# uv-exposure-box-main-v2.net
KiCad netlist of a schematic drawn in EAGLE
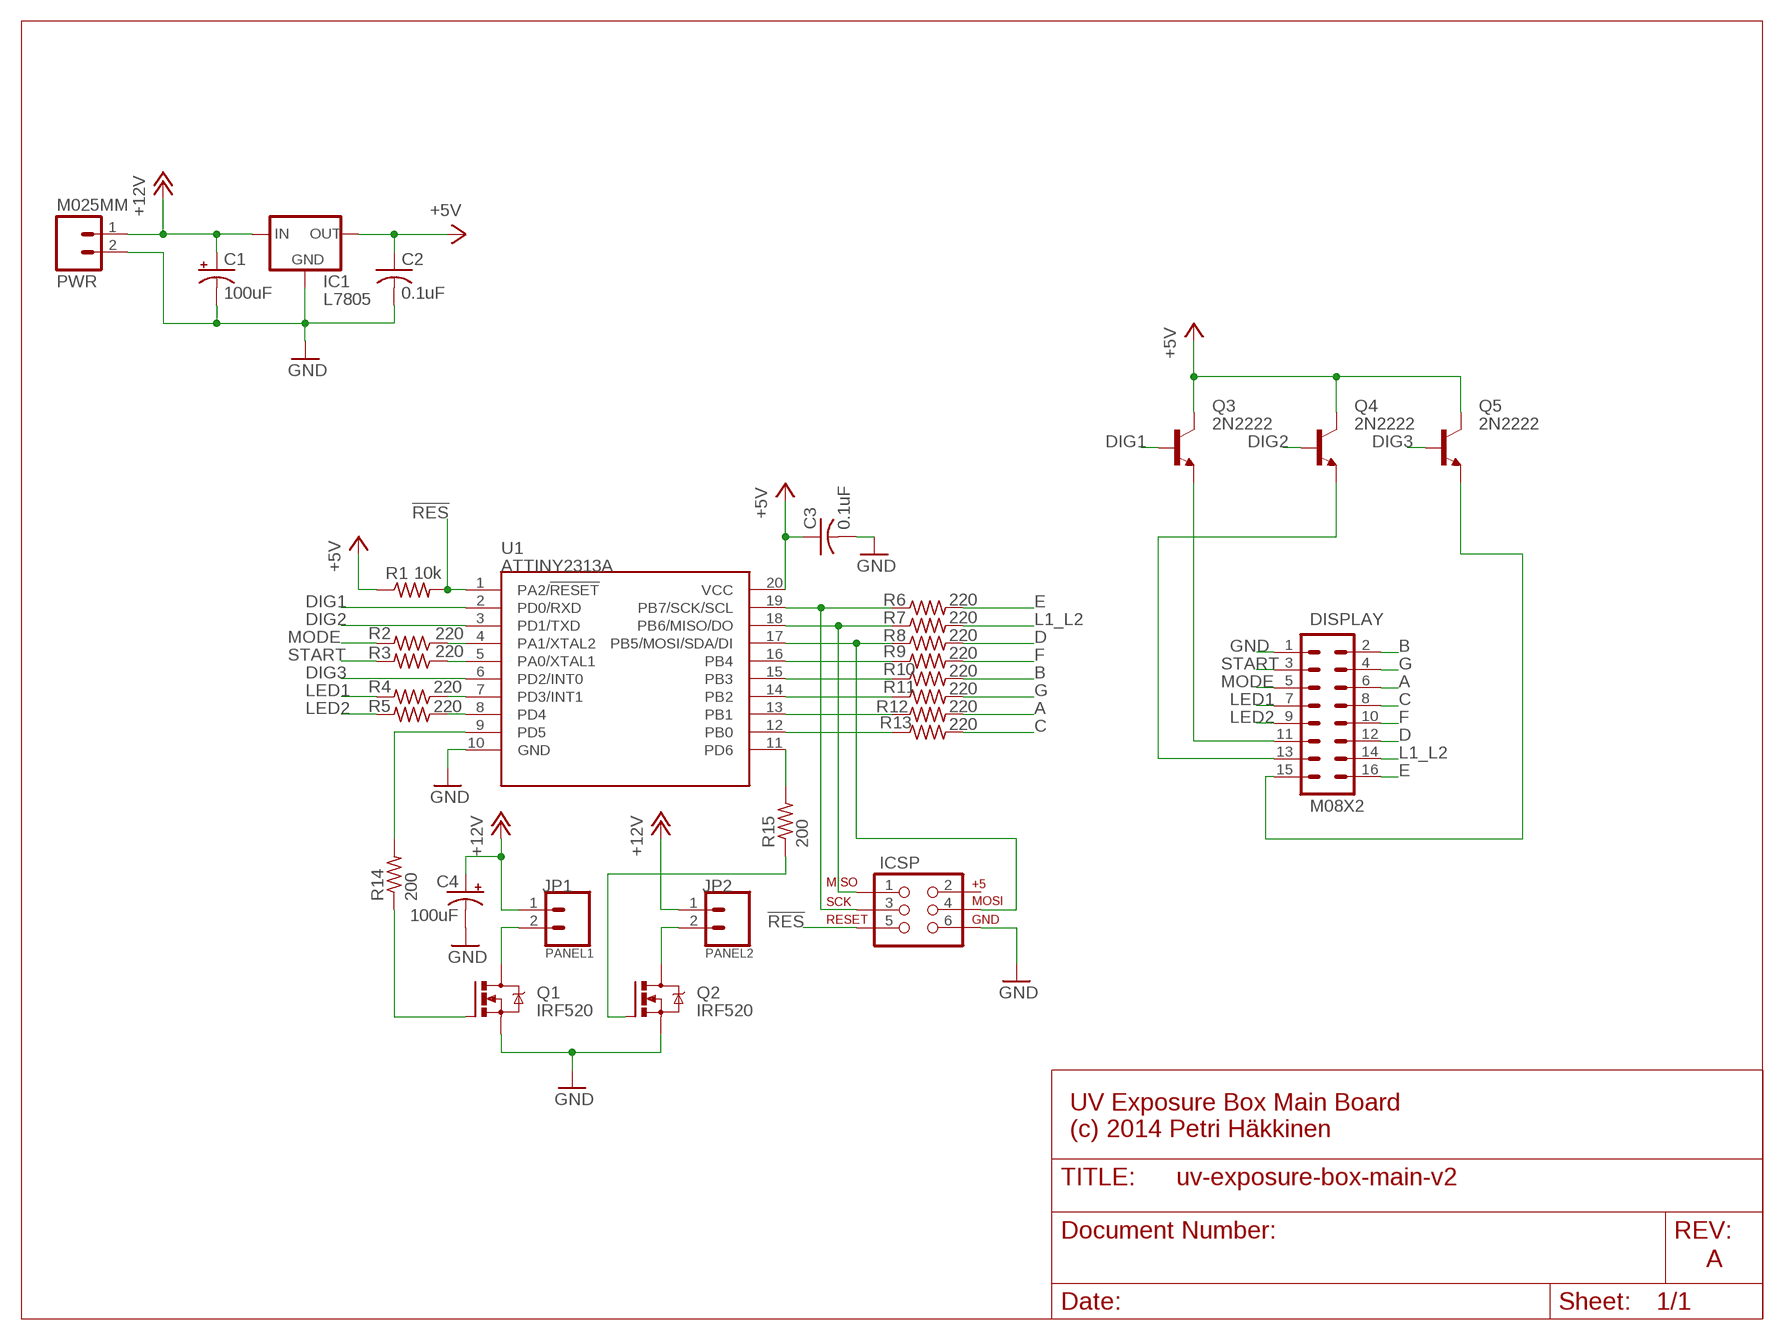
[diagram p0: schematic, sheet 1]

(export (version "E")
  (design (tool "Eeschema 10.0.6"))
  (components
    (comp (ref "C1")
      (value "100uF")
      (footprint "eagle-import:E2,5-5")
      (libsource (lib "eagle-import") (part "CPOL-USE2.5-5"))
    )
    (comp (ref "C2")
      (value "0.1uF")
      (footprint "eagle-import:C025-024X044")
      (libsource (lib "eagle-import") (part "C-US025-024X044"))
    )
    (comp (ref "C3")
      (value "0.1uF")
      (footprint "eagle-import:C025-024X044")
      (libsource (lib "eagle-import") (part "C-US025-024X044"))
    )
    (comp (ref "C4")
      (value "100uF")
      (footprint "eagle-import:E2,5-5")
      (libsource (lib "eagle-import") (part "CPOL-USE2.5-5"))
    )
    (comp (ref "DISPLAY")
      (value "M08X2")
      (footprint "eagle-import:2X8")
      (libsource (lib "eagle-import") (part "M08X2"))
    )
    (comp (ref "IC1")
      (value "L7805")
      (footprint "eagle-import:TO220-IGO")
      (libsource (lib "eagle-import") (part "V_REG_78XXV"))
    )
    (comp (ref "ICSP")
      (value "AVR_SPI_PRG_6PTH")
      (footprint "eagle-import:2X3")
      (libsource (lib "eagle-import") (part "AVR_SPI_PRG_6PTH"))
    )
    (comp (ref "JP1")
      (value "M025MM")
      (footprint "eagle-import:SCREWTERMINAL-5MM-2")
      (libsource (lib "eagle-import") (part "M025MM"))
    )
    (comp (ref "JP2")
      (value "M025MM")
      (footprint "eagle-import:SCREWTERMINAL-5MM-2")
      (libsource (lib "eagle-import") (part "M025MM"))
    )
    (comp (ref "PWR")
      (value "M025MM")
      (footprint "eagle-import:SCREWTERMINAL-5MM-2")
      (libsource (lib "eagle-import") (part "M025MM"))
    )
    (comp (ref "Q1")
      (value "IRF520")
      (footprint "eagle-import:TO220BV")
      (libsource (lib "eagle-import") (part "IRF520"))
    )
    (comp (ref "Q2")
      (value "IRF520")
      (footprint "eagle-import:TO220BV")
      (libsource (lib "eagle-import") (part "IRF520"))
    )
    (comp (ref "Q3")
      (value "2N2222")
      (footprint "eagle-import:TO92-EBC")
      (libsource (lib "eagle-import") (part "-NPN-TO92-EBC2N2222"))
    )
    (comp (ref "Q4")
      (value "2N2222")
      (footprint "eagle-import:TO92-EBC")
      (libsource (lib "eagle-import") (part "-NPN-TO92-EBC2N2222"))
    )
    (comp (ref "Q5")
      (value "2N2222")
      (footprint "eagle-import:TO92-EBC")
      (libsource (lib "eagle-import") (part "-NPN-TO92-EBC2N2222"))
    )
    (comp (ref "R1")
      (value "10k")
      (footprint "eagle-import:0207_10")
      (libsource (lib "eagle-import") (part "R-US_0207/10"))
    )
    (comp (ref "R2")
      (value "220")
      (footprint "eagle-import:0207_10")
      (libsource (lib "eagle-import") (part "R-US_0207/10"))
    )
    (comp (ref "R3")
      (value "220")
      (footprint "eagle-import:0207_10")
      (libsource (lib "eagle-import") (part "R-US_0207/10"))
    )
    (comp (ref "R4")
      (value "220")
      (footprint "eagle-import:0207_10")
      (libsource (lib "eagle-import") (part "R-US_0207/10"))
    )
    (comp (ref "R5")
      (value "220")
      (footprint "eagle-import:0207_10")
      (libsource (lib "eagle-import") (part "R-US_0207/10"))
    )
    (comp (ref "R6")
      (value "220")
      (footprint "eagle-import:0207_10")
      (libsource (lib "eagle-import") (part "R-US_0207/10"))
    )
    (comp (ref "R7")
      (value "220")
      (footprint "eagle-import:0207_10")
      (libsource (lib "eagle-import") (part "R-US_0207/10"))
    )
    (comp (ref "R8")
      (value "220")
      (footprint "eagle-import:0207_10")
      (libsource (lib "eagle-import") (part "R-US_0207/10"))
    )
    (comp (ref "R9")
      (value "220")
      (footprint "eagle-import:0207_10")
      (libsource (lib "eagle-import") (part "R-US_0207/10"))
    )
    (comp (ref "R10")
      (value "220")
      (footprint "eagle-import:0207_10")
      (libsource (lib "eagle-import") (part "R-US_0207/10"))
    )
    (comp (ref "R11")
      (value "220")
      (footprint "eagle-import:0207_10")
      (libsource (lib "eagle-import") (part "R-US_0207/10"))
    )
    (comp (ref "R12")
      (value "220")
      (footprint "eagle-import:0207_10")
      (libsource (lib "eagle-import") (part "R-US_0207/10"))
    )
    (comp (ref "R13")
      (value "220")
      (footprint "eagle-import:0207_10")
      (libsource (lib "eagle-import") (part "R-US_0207/10"))
    )
    (comp (ref "R14")
      (value "200")
      (footprint "eagle-import:0207_10")
      (libsource (lib "eagle-import") (part "R-US_0207/10"))
    )
    (comp (ref "R15")
      (value "200")
      (footprint "eagle-import:0207_10")
      (libsource (lib "eagle-import") (part "R-US_0207/10"))
    )
    (comp (ref "U1")
      (value "ATTINY2313A")
      (footprint "eagle-import:DIL20")
      (libsource (lib "eagle-import") (part "ATTINY2313ADIL20"))
    )
  )
  (nets
    (net (code "1") (name "+5V") (class "Default")
      (node (ref "C2") (pin "1") (pinfunction "1_1") (pintype "passive"))
      (node (ref "C3") (pin "1") (pinfunction "1_1") (pintype "passive"))
      (node (ref "IC1") (pin "OUT") (pinfunction "OUT_OUT") (pintype "output"))
      (node (ref "Q3") (pin "C") (pinfunction "C_C") (pintype "passive"))
      (node (ref "Q4") (pin "C") (pinfunction "C_C") (pintype "passive"))
      (node (ref "Q5") (pin "C") (pinfunction "C_C") (pintype "passive"))
      (node (ref "R1") (pin "1") (pinfunction "1_1") (pintype "passive"))
      (node (ref "U1") (pin "20") (pinfunction "VCC_20") (pintype "bidirectional"))
    )
    (net (code "2") (name "+12V") (class "Default")
      (node (ref "C1") (pin "+") (pinfunction "+_+") (pintype "passive"))
      (node (ref "C4") (pin "+") (pinfunction "+_+") (pintype "passive"))
      (node (ref "IC1") (pin "IN") (pinfunction "IN_IN") (pintype "input"))
      (node (ref "JP1") (pin "1") (pinfunction "1_1") (pintype "passive"))
      (node (ref "JP2") (pin "1") (pinfunction "1_1") (pintype "passive"))
      (node (ref "PWR") (pin "1") (pinfunction "1_1") (pintype "passive"))
    )
    (net (code "3") (name "/A") (class "Default")
      (node (ref "DISPLAY") (pin "6") (pinfunction "6_6") (pintype "passive"))
      (node (ref "R12") (pin "2") (pinfunction "2_2") (pintype "passive"))
    )
    (net (code "4") (name "/B") (class "Default")
      (node (ref "DISPLAY") (pin "2") (pinfunction "2_2") (pintype "passive"))
      (node (ref "R10") (pin "2") (pinfunction "2_2") (pintype "passive"))
    )
    (net (code "5") (name "/C") (class "Default")
      (node (ref "DISPLAY") (pin "8") (pinfunction "8_8") (pintype "passive"))
      (node (ref "R13") (pin "2") (pinfunction "2_2") (pintype "passive"))
    )
    (net (code "6") (name "/D") (class "Default")
      (node (ref "DISPLAY") (pin "12") (pinfunction "12_12") (pintype "passive"))
      (node (ref "R8") (pin "2") (pinfunction "2_2") (pintype "passive"))
    )
    (net (code "7") (name "/DIG1") (class "Default")
      (node (ref "DISPLAY") (pin "11") (pinfunction "11_11") (pintype "passive"))
      (node (ref "Q3") (pin "B") (pinfunction "B_B") (pintype "passive"))
      (node (ref "Q3") (pin "E") (pinfunction "E_E") (pintype "passive"))
      (node (ref "U1") (pin "2") (pinfunction "PD0/RXD_2") (pintype "bidirectional"))
    )
    (net (code "8") (name "/DIG2") (class "Default")
      (node (ref "Q4") (pin "B") (pinfunction "B_B") (pintype "passive"))
      (node (ref "U1") (pin "3") (pinfunction "PD1/TXD_3") (pintype "bidirectional"))
    )
    (net (code "9") (name "/DIG3") (class "Default")
      (node (ref "Q5") (pin "B") (pinfunction "B_B") (pintype "passive"))
      (node (ref "U1") (pin "6") (pinfunction "PD2/INT0_6") (pintype "bidirectional"))
    )
    (net (code "10") (name "/E") (class "Default")
      (node (ref "DISPLAY") (pin "16") (pinfunction "16_16") (pintype "passive"))
      (node (ref "R6") (pin "2") (pinfunction "2_2") (pintype "passive"))
    )
    (net (code "11") (name "/F") (class "Default")
      (node (ref "DISPLAY") (pin "10") (pinfunction "10_10") (pintype "passive"))
      (node (ref "R9") (pin "2") (pinfunction "2_2") (pintype "passive"))
    )
    (net (code "12") (name "/G") (class "Default")
      (node (ref "DISPLAY") (pin "4") (pinfunction "4_4") (pintype "passive"))
      (node (ref "R11") (pin "2") (pinfunction "2_2") (pintype "passive"))
    )
    (net (code "13") (name "/L1_L2") (class "Default")
      (node (ref "DISPLAY") (pin "14") (pinfunction "14_14") (pintype "passive"))
      (node (ref "R7") (pin "2") (pinfunction "2_2") (pintype "passive"))
    )
    (net (code "14") (name "/LED1") (class "Default")
      (node (ref "DISPLAY") (pin "7") (pinfunction "7_7") (pintype "passive"))
      (node (ref "R4") (pin "2") (pinfunction "2_2") (pintype "passive"))
    )
    (net (code "15") (name "/LED2") (class "Default")
      (node (ref "DISPLAY") (pin "9") (pinfunction "9_9") (pintype "passive"))
      (node (ref "R5") (pin "2") (pinfunction "2_2") (pintype "passive"))
    )
    (net (code "16") (name "/MODE") (class "Default")
      (node (ref "DISPLAY") (pin "5") (pinfunction "5_5") (pintype "passive"))
      (node (ref "R2") (pin "2") (pinfunction "2_2") (pintype "passive"))
    )
    (net (code "17") (name "/START") (class "Default")
      (node (ref "DISPLAY") (pin "3") (pinfunction "3_3") (pintype "passive"))
      (node (ref "R3") (pin "2") (pinfunction "2_2") (pintype "passive"))
    )
    (net (code "18") (name "/~{RES}") (class "Default")
      (node (ref "ICSP") (pin "5") (pinfunction "5_5") (pintype "passive"))
      (node (ref "R1") (pin "2") (pinfunction "2_2") (pintype "passive"))
      (node (ref "U1") (pin "1") (pinfunction "PA2/~{RESET}_1") (pintype "bidirectional"))
    )
    (net (code "19") (name "GND") (class "Default")
      (node (ref "C1") (pin "-") (pinfunction "-_-") (pintype "passive"))
      (node (ref "C2") (pin "2") (pinfunction "2_2") (pintype "passive"))
      (node (ref "C3") (pin "2") (pinfunction "2_2") (pintype "passive"))
      (node (ref "C4") (pin "-") (pinfunction "-_-") (pintype "passive"))
      (node (ref "DISPLAY") (pin "1") (pinfunction "1_1") (pintype "passive"))
      (node (ref "IC1") (pin "GND") (pinfunction "GND_GND") (pintype "input"))
      (node (ref "ICSP") (pin "6") (pinfunction "6_6") (pintype "passive"))
      (node (ref "PWR") (pin "2") (pinfunction "2_2") (pintype "passive"))
      (node (ref "Q1") (pin "S") (pinfunction "S_S") (pintype "passive"))
      (node (ref "Q2") (pin "S") (pinfunction "S_S") (pintype "passive"))
      (node (ref "U1") (pin "10") (pinfunction "GND_10") (pintype "bidirectional"))
    )
    (net (code "20") (name "Net-(DISPLAY-Pad13)") (class "Default")
      (node (ref "DISPLAY") (pin "13") (pinfunction "13_13") (pintype "passive"))
      (node (ref "Q4") (pin "E") (pinfunction "E_E") (pintype "passive"))
    )
    (net (code "21") (name "Net-(DISPLAY-Pad15)") (class "Default")
      (node (ref "DISPLAY") (pin "15") (pinfunction "15_15") (pintype "passive"))
      (node (ref "Q5") (pin "E") (pinfunction "E_E") (pintype "passive"))
    )
    (net (code "22") (name "Net-(JP1-Pad2)") (class "Default")
      (node (ref "JP1") (pin "2") (pinfunction "2_2") (pintype "passive"))
      (node (ref "Q1") (pin "D") (pinfunction "D_D") (pintype "passive"))
    )
    (net (code "23") (name "Net-(JP2-Pad2)") (class "Default")
      (node (ref "JP2") (pin "2") (pinfunction "2_2") (pintype "passive"))
      (node (ref "Q2") (pin "D") (pinfunction "D_D") (pintype "passive"))
    )
    (net (code "24") (name "Net-(Q1-PadG)") (class "Default")
      (node (ref "Q1") (pin "G") (pinfunction "G_G") (pintype "passive"))
      (node (ref "R14") (pin "1") (pinfunction "1_1") (pintype "passive"))
    )
    (net (code "25") (name "Net-(Q2-PadG)") (class "Default")
      (node (ref "Q2") (pin "G") (pinfunction "G_G") (pintype "passive"))
      (node (ref "R15") (pin "1") (pinfunction "1_1") (pintype "passive"))
    )
    (net (code "26") (name "Net-(U1-PA0{slash}XTAL1)") (class "Default")
      (node (ref "R3") (pin "1") (pinfunction "1_1") (pintype "passive"))
      (node (ref "U1") (pin "5") (pinfunction "PA0/XTAL1_5") (pintype "bidirectional"))
    )
    (net (code "27") (name "Net-(U1-PA1{slash}XTAL2)") (class "Default")
      (node (ref "R2") (pin "1") (pinfunction "1_1") (pintype "passive"))
      (node (ref "U1") (pin "4") (pinfunction "PA1/XTAL2_4") (pintype "bidirectional"))
    )
    (net (code "28") (name "Net-(U1-PB0)") (class "Default")
      (node (ref "R13") (pin "1") (pinfunction "1_1") (pintype "passive"))
      (node (ref "U1") (pin "12") (pinfunction "PB0_12") (pintype "bidirectional"))
    )
    (net (code "29") (name "Net-(U1-PB1)") (class "Default")
      (node (ref "R12") (pin "1") (pinfunction "1_1") (pintype "passive"))
      (node (ref "U1") (pin "13") (pinfunction "PB1_13") (pintype "bidirectional"))
    )
    (net (code "30") (name "Net-(U1-PB2)") (class "Default")
      (node (ref "R11") (pin "1") (pinfunction "1_1") (pintype "passive"))
      (node (ref "U1") (pin "14") (pinfunction "PB2_14") (pintype "bidirectional"))
    )
    (net (code "31") (name "Net-(U1-PB3)") (class "Default")
      (node (ref "R10") (pin "1") (pinfunction "1_1") (pintype "passive"))
      (node (ref "U1") (pin "15") (pinfunction "PB3_15") (pintype "bidirectional"))
    )
    (net (code "32") (name "Net-(U1-PB4)") (class "Default")
      (node (ref "R9") (pin "1") (pinfunction "1_1") (pintype "passive"))
      (node (ref "U1") (pin "16") (pinfunction "PB4_16") (pintype "bidirectional"))
    )
    (net (code "33") (name "Net-(U1-PB5{slash}MOSI{slash}SDA{slash}DI)") (class "Default")
      (node (ref "ICSP") (pin "4") (pinfunction "4_4") (pintype "passive"))
      (node (ref "R8") (pin "1") (pinfunction "1_1") (pintype "passive"))
      (node (ref "U1") (pin "17") (pinfunction "PB5/MOSI/SDA/DI_17") (pintype "bidirectional"))
    )
    (net (code "34") (name "Net-(U1-PB6{slash}MISO{slash}DO)") (class "Default")
      (node (ref "ICSP") (pin "1") (pinfunction "1_1") (pintype "passive"))
      (node (ref "R7") (pin "1") (pinfunction "1_1") (pintype "passive"))
      (node (ref "U1") (pin "18") (pinfunction "PB6/MISO/DO_18") (pintype "bidirectional"))
    )
    (net (code "35") (name "Net-(U1-PB7{slash}SCK{slash}SCL)") (class "Default")
      (node (ref "ICSP") (pin "3") (pinfunction "3_3") (pintype "passive"))
      (node (ref "R6") (pin "1") (pinfunction "1_1") (pintype "passive"))
      (node (ref "U1") (pin "19") (pinfunction "PB7/SCK/SCL_19") (pintype "bidirectional"))
    )
    (net (code "36") (name "Net-(U1-PD3{slash}INT1)") (class "Default")
      (node (ref "R4") (pin "1") (pinfunction "1_1") (pintype "passive"))
      (node (ref "U1") (pin "7") (pinfunction "PD3/INT1_7") (pintype "bidirectional"))
    )
    (net (code "37") (name "Net-(U1-PD4)") (class "Default")
      (node (ref "R5") (pin "1") (pinfunction "1_1") (pintype "passive"))
      (node (ref "U1") (pin "8") (pinfunction "PD4_8") (pintype "bidirectional"))
    )
    (net (code "38") (name "Net-(U1-PD5)") (class "Default")
      (node (ref "R14") (pin "2") (pinfunction "2_2") (pintype "passive"))
      (node (ref "U1") (pin "9") (pinfunction "PD5_9") (pintype "bidirectional"))
    )
    (net (code "39") (name "Net-(U1-PD6)") (class "Default")
      (node (ref "R15") (pin "2") (pinfunction "2_2") (pintype "passive"))
      (node (ref "U1") (pin "11") (pinfunction "PD6_11") (pintype "bidirectional"))
    )
    (net (code "40") (name "unconnected-(ICSP-Pad2)") (class "Default")
      (node (ref "ICSP") (pin "2") (pinfunction "2_2") (pintype "passive"))
    )
  )
)
